# PT1000_interface.net
KiCad netlist of a schematic drawn in Altium Designer
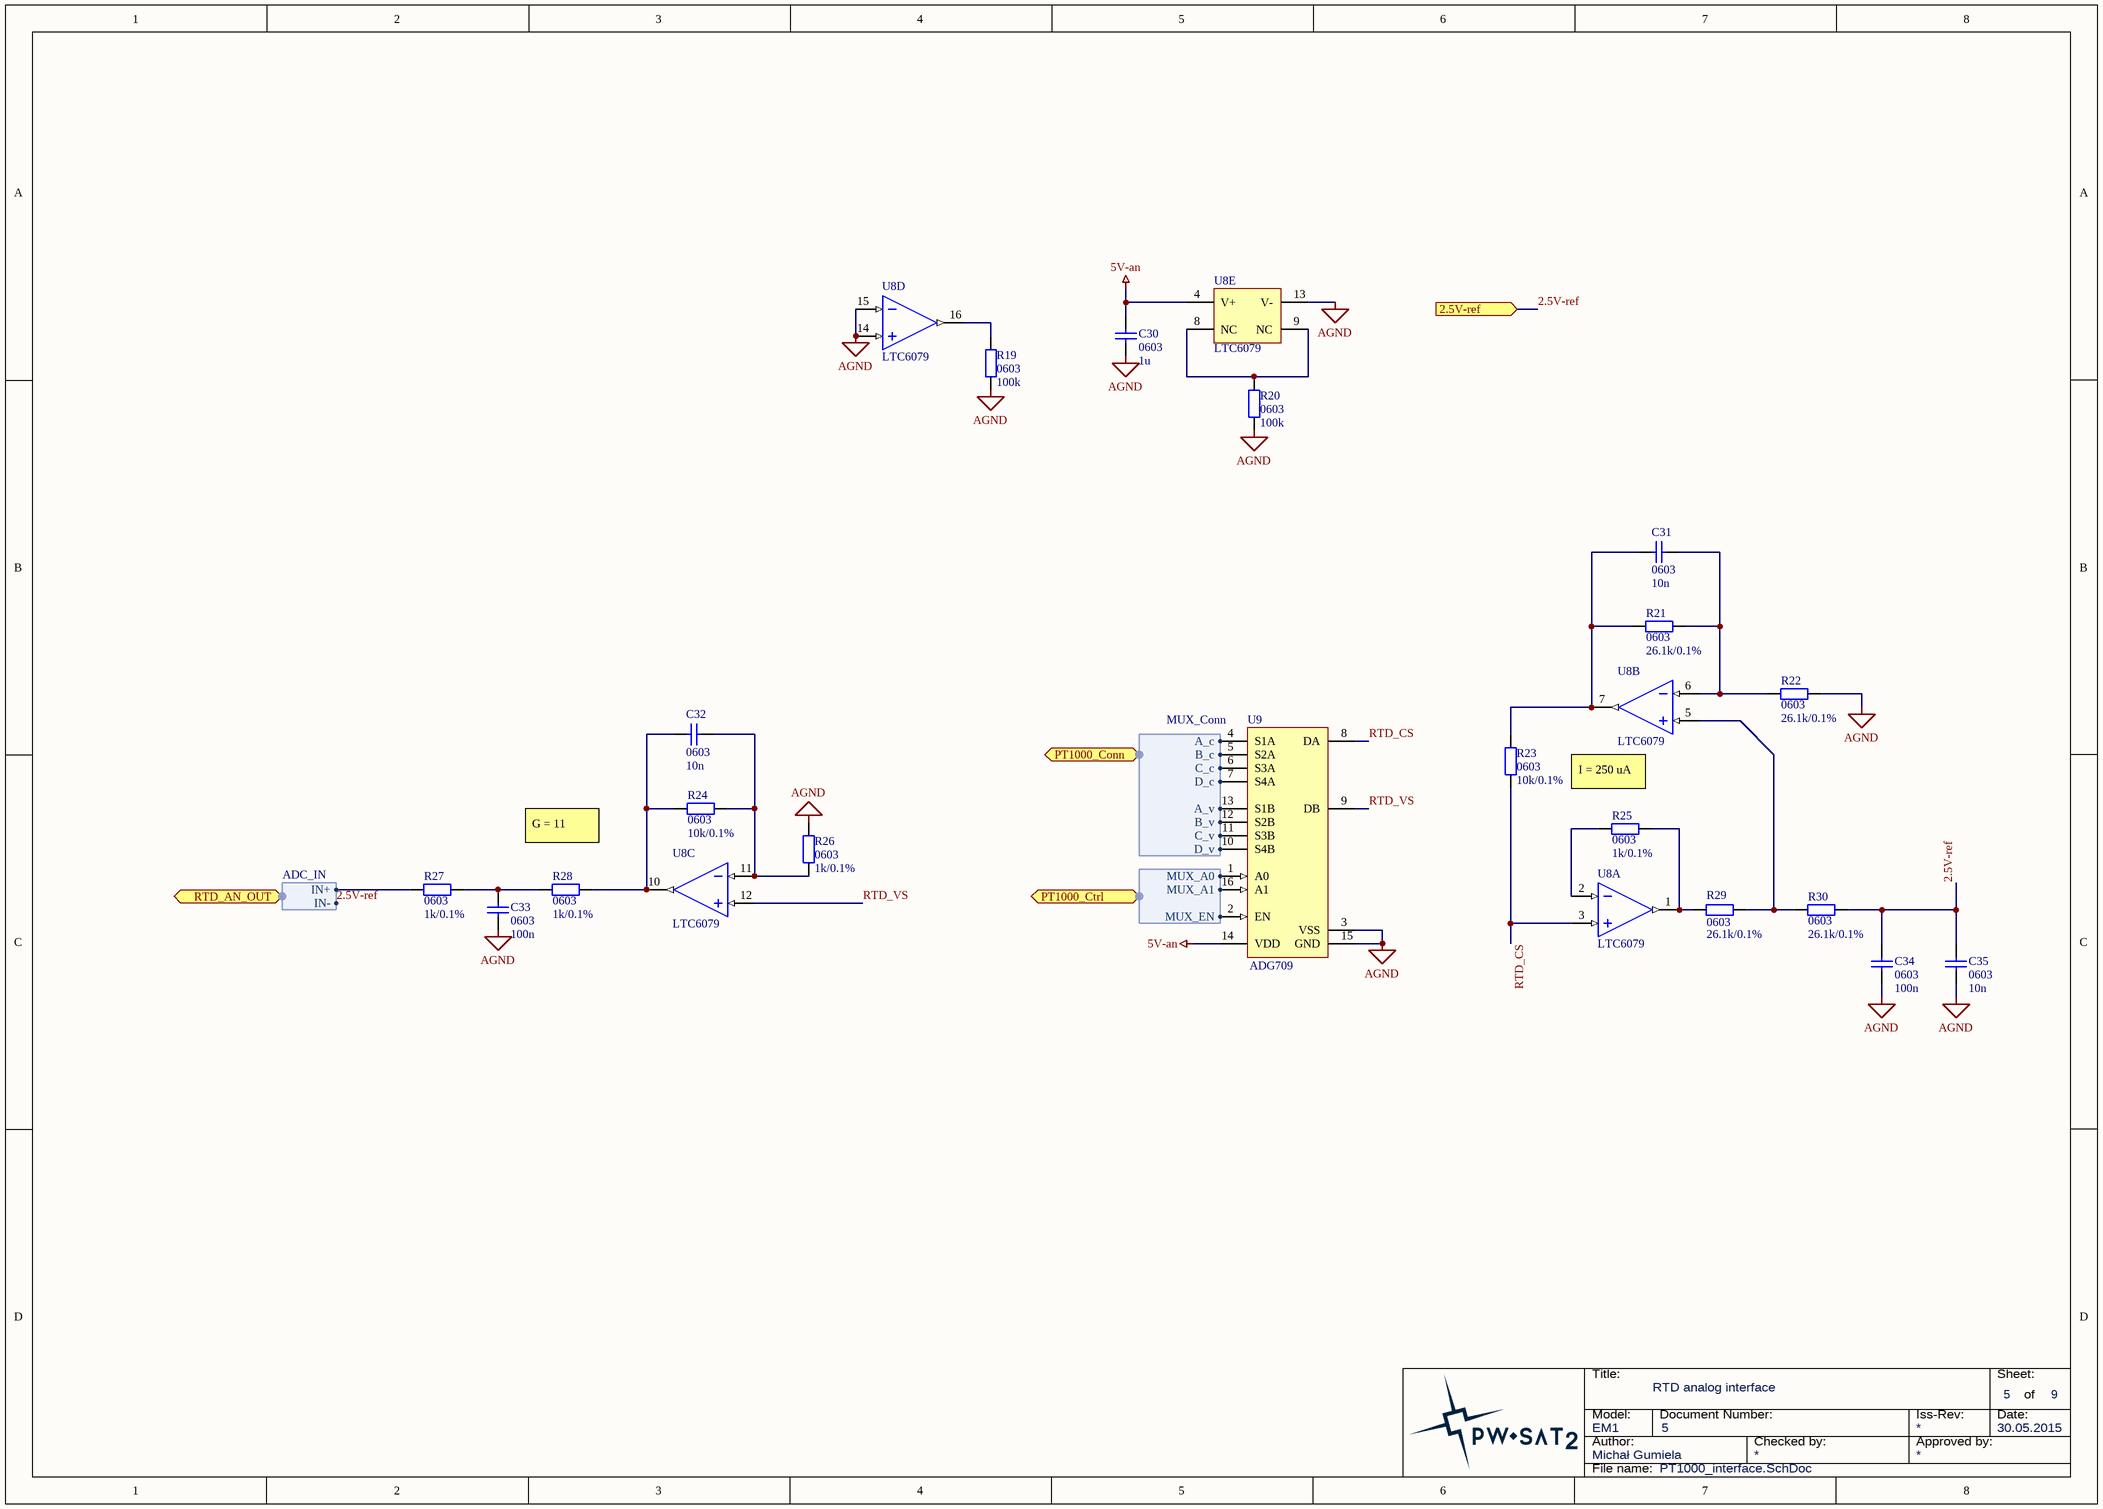
[diagram p0: PT1000_interface.SchDoc]

(export (version "E")
  (design (tool "Eeschema 10.0.6"))
  (components
    (comp (ref "C30")
      (value "0603")
      (footprint "SMD_Capacitor_0603")
      (description "Capacitor")
      (fields (field (name "ALTIUM_VALUE") "1u") (field (name "PUBLISHER") "Altium Limited"))
      (libsource (lib "Miscellaneous Devices") (part "Cap"))
    )
    (comp (ref "C31")
      (value "0603")
      (footprint "SMD_Capacitor_0603")
      (description "Capacitor")
      (fields (field (name "ALTIUM_VALUE") "10n") (field (name "PUBLISHER") "Altium Limited"))
      (libsource (lib "Miscellaneous Devices") (part "Cap"))
    )
    (comp (ref "C32")
      (value "0603")
      (footprint "SMD_Capacitor_0603")
      (description "Capacitor")
      (fields (field (name "ALTIUM_VALUE") "10n") (field (name "PUBLISHER") "Altium Limited"))
      (libsource (lib "Miscellaneous Devices") (part "Cap"))
    )
    (comp (ref "C33")
      (value "0603")
      (footprint "SMD_Capacitor_0603")
      (description "Capacitor")
      (fields (field (name "ALTIUM_VALUE") "100n") (field (name "PUBLISHER") "Altium Limited"))
      (libsource (lib "Miscellaneous Devices") (part "Cap"))
    )
    (comp (ref "C34")
      (value "0603")
      (footprint "SMD_Capacitor_0603")
      (description "Capacitor")
      (fields (field (name "ALTIUM_VALUE") "100n") (field (name "PUBLISHER") "Altium Limited"))
      (libsource (lib "Miscellaneous Devices") (part "Cap"))
    )
    (comp (ref "C35")
      (value "0603")
      (footprint "SMD_Capacitor_0603")
      (description "Capacitor")
      (fields (field (name "ALTIUM_VALUE") "10n") (field (name "PUBLISHER") "Altium Limited"))
      (libsource (lib "Miscellaneous Devices") (part "Cap"))
    )
    (comp (ref "R19")
      (value "0603")
      (footprint "SMD_Resistor_0603")
      (description "Resistor")
      (fields (field (name "ALTIUM_VALUE") "100k") (field (name "PUBLISHER") "Altium Limited"))
      (libsource (lib "") (part "Res2_2"))
    )
    (comp (ref "R20")
      (value "0603")
      (footprint "SMD_Resistor_0603")
      (description "Resistor")
      (fields (field (name "ALTIUM_VALUE") "100k") (field (name "PUBLISHER") "Altium Limited"))
      (libsource (lib "") (part "Res2_2"))
    )
    (comp (ref "R21")
      (value "0603")
      (footprint "SMD_Resistor_0603")
      (description "Resistor")
      (fields (field (name "ALTIUM_VALUE") "26.1k/0.1%") (field (name "PUBLISHER") "Altium Limited"))
      (libsource (lib "Miscellaneous Devices") (part "Res2"))
    )
    (comp (ref "R22")
      (value "0603")
      (footprint "SMD_Resistor_0603")
      (description "Resistor")
      (fields (field (name "ALTIUM_VALUE") "26.1k/0.1%") (field (name "PUBLISHER") "Altium Limited"))
      (libsource (lib "Miscellaneous Devices") (part "Res2"))
    )
    (comp (ref "R23")
      (value "0603")
      (footprint "SMD_Resistor_0603")
      (description "Resistor")
      (fields (field (name "ALTIUM_VALUE") "10k/0.1%") (field (name "PUBLISHER") "Altium Limited"))
      (libsource (lib "") (part "Res2_2"))
    )
    (comp (ref "R24")
      (value "0603")
      (footprint "SMD_Resistor_0603")
      (description "Resistor")
      (fields (field (name "ALTIUM_VALUE") "10k/0.1%") (field (name "PUBLISHER") "Altium Limited"))
      (libsource (lib "Miscellaneous Devices") (part "Res2"))
    )
    (comp (ref "R25")
      (value "0603")
      (footprint "SMD_Resistor_0603")
      (description "Resistor")
      (fields (field (name "ALTIUM_VALUE") "1k/0.1%") (field (name "PUBLISHER") "Altium Limited"))
      (libsource (lib "") (part "Res2_1"))
    )
    (comp (ref "R26")
      (value "0603")
      (footprint "SMD_Resistor_0603")
      (description "Resistor")
      (fields (field (name "ALTIUM_VALUE") "1k/0.1%") (field (name "PUBLISHER") "Altium Limited"))
      (libsource (lib "") (part "Res2_3"))
    )
    (comp (ref "R27")
      (value "0603")
      (footprint "SMD_Resistor_0603")
      (description "Resistor")
      (fields (field (name "ALTIUM_VALUE") "1k/0.1%") (field (name "PUBLISHER") "Altium Limited"))
      (libsource (lib "") (part "Res2_1"))
    )
    (comp (ref "R28")
      (value "0603")
      (footprint "SMD_Resistor_0603")
      (description "Resistor")
      (fields (field (name "ALTIUM_VALUE") "1k/0.1%") (field (name "PUBLISHER") "Altium Limited"))
      (libsource (lib "") (part "Res2_1"))
    )
    (comp (ref "R29")
      (value "0603")
      (footprint "SMD_Resistor_0603")
      (description "Resistor")
      (fields (field (name "ALTIUM_VALUE") "26.1k/0.1%") (field (name "PUBLISHER") "Altium Limited"))
      (libsource (lib "Miscellaneous Devices") (part "Res2"))
    )
    (comp (ref "R30")
      (value "0603")
      (footprint "SMD_Resistor_0603")
      (description "Resistor")
      (fields (field (name "ALTIUM_VALUE") "26.1k/0.1%") (field (name "PUBLISHER") "Altium Limited"))
      (libsource (lib "Miscellaneous Devices") (part "Res2"))
    )
    (comp (ref "U8")
      (value "LTC6079")
      (footprint "SSOP-16")
      (description "Rail-to-rail, quad operational amplifier. Library compatible with LTC608X LTC607X op-amps")
      (fields (field (name "MANUFACTURER") "Linear Technology"))
      (libsource (lib "") (part "LTC6079_1"))
    )
    (comp (ref "U9")
      (value "ADG709")
      (footprint "TSSOP16")
      (description "CMOS Analog 4-Channel Multiplexer")
      (fields (field (name "MANUFACTURER") "Analog Devices") (field (name "MANUFACTURERPARTNUMBER") "ADG709"))
      (libsource (lib "microcircuits_miscellaneous") (part "ADG709"))
    )
  )
  (nets
    (net (code "4") (name "/2.5V-ref") (class "Default")
      (node (ref "C34") (pin "2") (pinfunction "2_2") (pintype "passive"))
      (node (ref "C35") (pin "2") (pinfunction "2_2") (pintype "passive"))
      (node (ref "R30") (pin "1") (pinfunction "1_1") (pintype "passive"))
    )
    (net (code "5") (name "/A_c") (class "Default")
      (node (ref "U9") (pin "4") (pinfunction "S1A_4") (pintype "passive"))
    )
    (net (code "6") (name "/A_v") (class "Default")
      (node (ref "U9") (pin "13") (pinfunction "S1B_13") (pintype "passive"))
    )
    (net (code "7") (name "/B_c") (class "Default")
      (node (ref "U9") (pin "5") (pinfunction "S2A_5") (pintype "passive"))
    )
    (net (code "8") (name "/B_v") (class "Default")
      (node (ref "U9") (pin "12") (pinfunction "S2B_12") (pintype "passive"))
    )
    (net (code "9") (name "/C_c") (class "Default")
      (node (ref "U9") (pin "6") (pinfunction "S3A_6") (pintype "passive"))
    )
    (net (code "10") (name "/C_v") (class "Default")
      (node (ref "U9") (pin "11") (pinfunction "S3B_11") (pintype "passive"))
    )
    (net (code "11") (name "/D_c") (class "Default")
      (node (ref "U9") (pin "7") (pinfunction "S4A_7") (pintype "passive"))
    )
    (net (code "12") (name "/D_v") (class "Default")
      (node (ref "U9") (pin "10") (pinfunction "S4B_10") (pintype "passive"))
    )
    (net (code "13") (name "/IN+") (class "Default")
      (node (ref "R27") (pin "1") (pinfunction "1_1") (pintype "passive"))
    )
    (net (code "14") (name "/MUX_A0") (class "Default")
      (node (ref "U9") (pin "1") (pinfunction "A0_1") (pintype "input"))
    )
    (net (code "15") (name "/MUX_A1") (class "Default")
      (node (ref "U9") (pin "16") (pinfunction "A1_16") (pintype "input"))
    )
    (net (code "16") (name "/MUX_EN") (class "Default")
      (node (ref "U9") (pin "2") (pinfunction "EN_2") (pintype "input"))
    )
    (net (code "17") (name "/RTD_CS") (class "Default")
      (node (ref "R23") (pin "1") (pinfunction "1_1") (pintype "passive"))
      (node (ref "U8") (pin "3") (pinfunction "IN+_A_3") (pintype "input"))
      (node (ref "U9") (pin "8") (pinfunction "DA_8") (pintype "passive"))
    )
    (net (code "18") (name "/RTD_VS") (class "Default")
      (node (ref "U8") (pin "12") (pinfunction "IN+_C_12") (pintype "input"))
      (node (ref "U9") (pin "9") (pinfunction "DB_9") (pintype "passive"))
    )
    (net (code "22") (name "5V-an") (class "Default")
      (node (ref "C30") (pin "2") (pinfunction "2_2") (pintype "passive"))
      (node (ref "U8") (pin "4") (pinfunction "V+_4") (pintype "power_in"))
      (node (ref "U9") (pin "14") (pinfunction "VDD_14") (pintype "power_in"))
    )
    (net (code "23") (name "AGND") (class "Default")
      (node (ref "C30") (pin "1") (pinfunction "1_1") (pintype "passive"))
      (node (ref "C33") (pin "1") (pinfunction "1_1") (pintype "passive"))
      (node (ref "C34") (pin "1") (pinfunction "1_1") (pintype "passive"))
      (node (ref "C35") (pin "1") (pinfunction "1_1") (pintype "passive"))
      (node (ref "R19") (pin "1") (pinfunction "1_1") (pintype "passive"))
      (node (ref "R20") (pin "1") (pinfunction "1_1") (pintype "passive"))
      (node (ref "R22") (pin "1") (pinfunction "1_1") (pintype "passive"))
      (node (ref "R26") (pin "1") (pinfunction "1_1") (pintype "passive"))
      (node (ref "U8") (pin "13") (pinfunction "V-_13") (pintype "power_in"))
      (node (ref "U8") (pin "14") (pinfunction "IN+_D_14") (pintype "input"))
      (node (ref "U8") (pin "15") (pinfunction "IN-_D_15") (pintype "input"))
      (node (ref "U9") (pin "15") (pinfunction "GND_15") (pintype "power_in"))
      (node (ref "U9") (pin "3") (pinfunction "VSS_3") (pintype "power_in"))
    )
    (net (code "24") (name "Net-(C33-Pad2)") (class "Default")
      (node (ref "C33") (pin "2") (pinfunction "2_2") (pintype "passive"))
      (node (ref "R27") (pin "2") (pinfunction "2_2") (pintype "passive"))
      (node (ref "R28") (pin "1") (pinfunction "1_1") (pintype "passive"))
    )
    (net (code "25") (name "Net-(R20-Pad2)") (class "Default")
      (node (ref "R20") (pin "2") (pinfunction "2_2") (pintype "passive"))
      (node (ref "U8") (pin "8") (pinfunction "NC_8") (pintype "passive"))
      (node (ref "U8") (pin "9") (pinfunction "NC_9") (pintype "passive"))
    )
    (net (code "26") (name "Net-(U8A-IN-_A)") (class "Default")
      (node (ref "R25") (pin "1") (pinfunction "1_1") (pintype "passive"))
      (node (ref "U8") (pin "2") (pinfunction "IN-_A_2") (pintype "input"))
    )
    (net (code "27") (name "Net-(U8A-OUT_A)") (class "Default")
      (node (ref "R25") (pin "2") (pinfunction "2_2") (pintype "passive"))
      (node (ref "R29") (pin "2") (pinfunction "2_2") (pintype "passive"))
      (node (ref "U8") (pin "1") (pinfunction "OUT_A_1") (pintype "output"))
    )
    (net (code "28") (name "Net-(U8B-IN+_B)") (class "Default")
      (node (ref "R29") (pin "1") (pinfunction "1_1") (pintype "passive"))
      (node (ref "R30") (pin "2") (pinfunction "2_2") (pintype "passive"))
      (node (ref "U8") (pin "5") (pinfunction "IN+_B_5") (pintype "input"))
    )
    (net (code "29") (name "Net-(U8B-IN-_B)") (class "Default")
      (node (ref "C31") (pin "1") (pinfunction "1_1") (pintype "passive"))
      (node (ref "R21") (pin "1") (pinfunction "1_1") (pintype "passive"))
      (node (ref "R22") (pin "2") (pinfunction "2_2") (pintype "passive"))
      (node (ref "U8") (pin "6") (pinfunction "IN-_B_6") (pintype "input"))
    )
    (net (code "30") (name "Net-(U8B-OUT_B)") (class "Default")
      (node (ref "C31") (pin "2") (pinfunction "2_2") (pintype "passive"))
      (node (ref "R21") (pin "2") (pinfunction "2_2") (pintype "passive"))
      (node (ref "R23") (pin "2") (pinfunction "2_2") (pintype "passive"))
      (node (ref "U8") (pin "7") (pinfunction "OUT_B_7") (pintype "output"))
    )
    (net (code "31") (name "Net-(U8C-IN-_C)") (class "Default")
      (node (ref "C32") (pin "1") (pinfunction "1_1") (pintype "passive"))
      (node (ref "R24") (pin "1") (pinfunction "1_1") (pintype "passive"))
      (node (ref "R26") (pin "2") (pinfunction "2_2") (pintype "passive"))
      (node (ref "U8") (pin "11") (pinfunction "IN-_C_11") (pintype "input"))
    )
    (net (code "32") (name "Net-(U8C-OUT_C)") (class "Default")
      (node (ref "C32") (pin "2") (pinfunction "2_2") (pintype "passive"))
      (node (ref "R24") (pin "2") (pinfunction "2_2") (pintype "passive"))
      (node (ref "R28") (pin "2") (pinfunction "2_2") (pintype "passive"))
      (node (ref "U8") (pin "10") (pinfunction "OUT_C_10") (pintype "output"))
    )
    (net (code "33") (name "Net-(U8D-OUT_D)") (class "Default")
      (node (ref "R19") (pin "2") (pinfunction "2_2") (pintype "passive"))
      (node (ref "U8") (pin "16") (pinfunction "OUT_D_16") (pintype "output"))
    )
  )
)
